# ICP_XMega.net
KiCad netlist of a schematic drawn in EAGLE
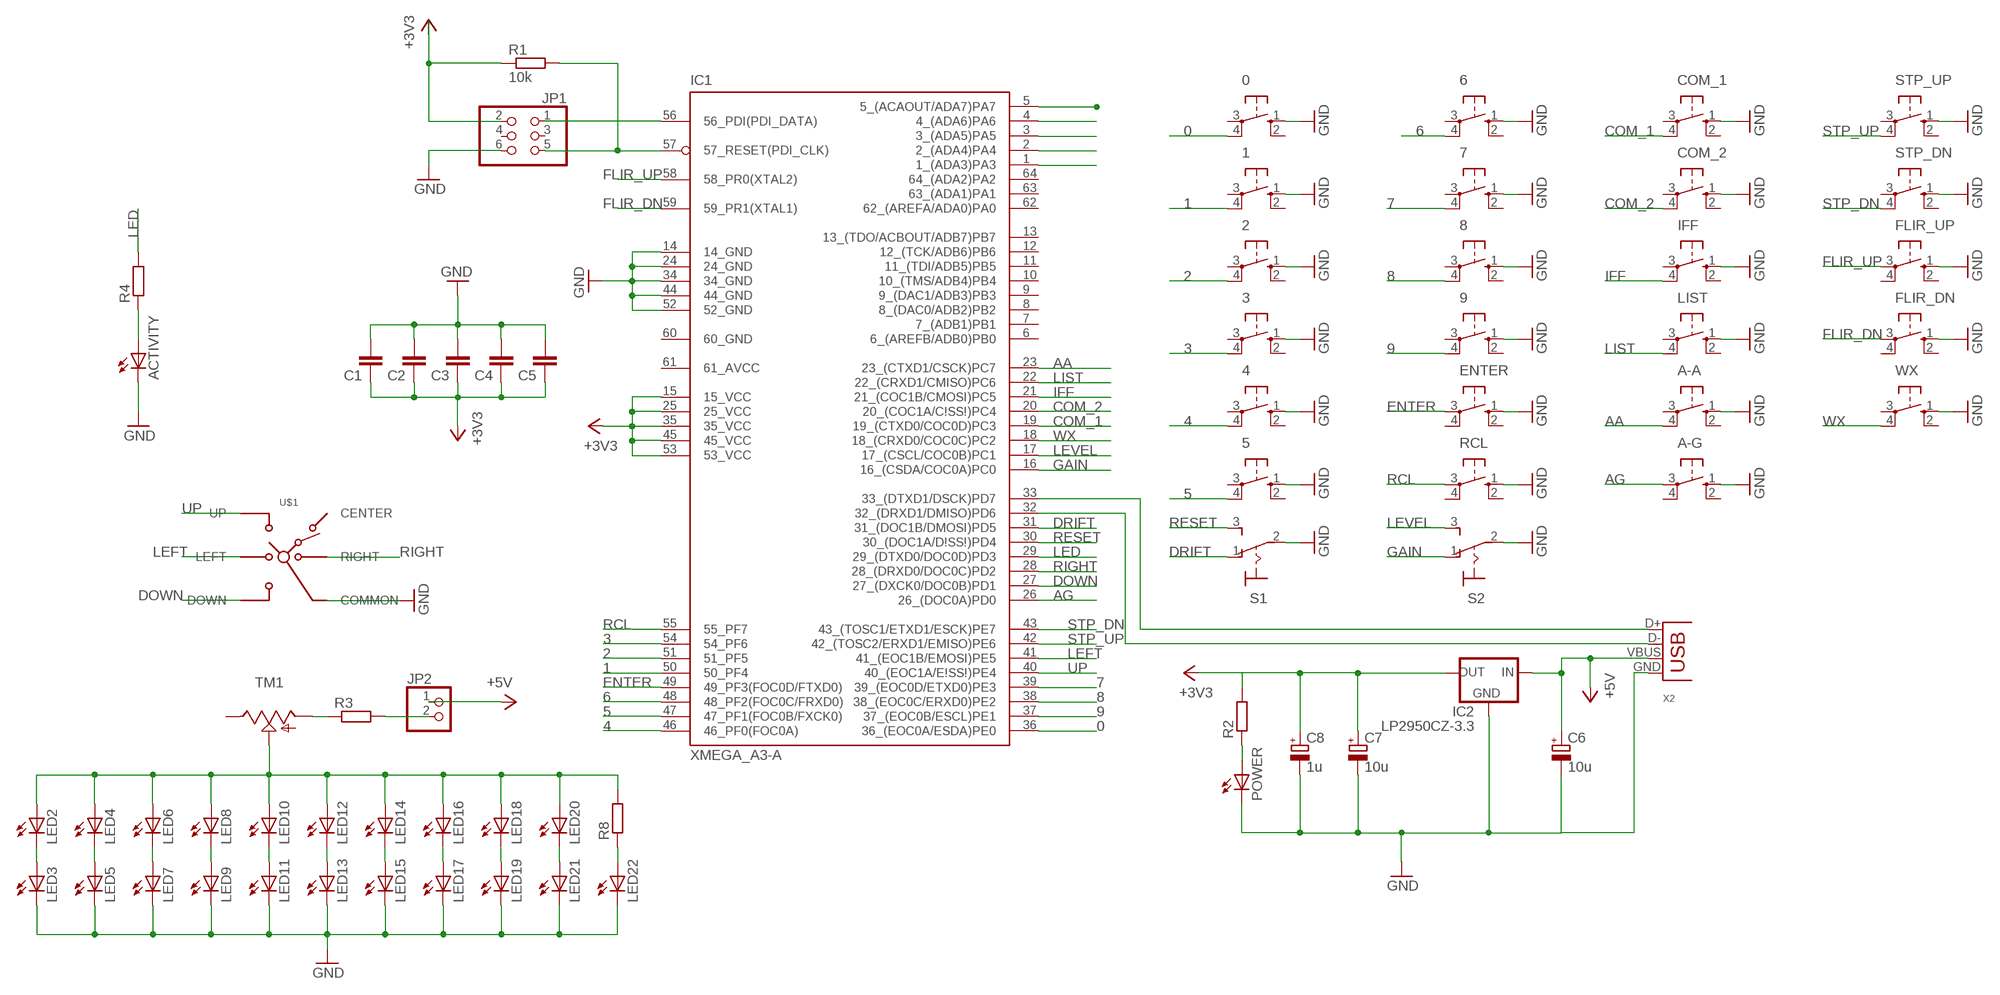
[diagram p0: schematic, sheet 1]

(export (version "E")
  (design (tool "Eeschema 10.0.6"))
  (components
    (comp (ref "0")
      (value "10-XX")
      (footprint "eagle-import:B3F-10XX")
      (fields (field (name "MPN") "B3F-1000"))
      (libsource (lib "eagle-import") (part "10-XX"))
    )
    (comp (ref "1")
      (value "10-XX")
      (footprint "eagle-import:B3F-10XX")
      (fields (field (name "MPN") "B3F-1000"))
      (libsource (lib "eagle-import") (part "10-XX"))
    )
    (comp (ref "2")
      (value "10-XX")
      (footprint "eagle-import:B3F-10XX")
      (fields (field (name "MPN") "B3F-1000"))
      (libsource (lib "eagle-import") (part "10-XX"))
    )
    (comp (ref "3")
      (value "10-XX")
      (footprint "eagle-import:B3F-10XX")
      (fields (field (name "MPN") "B3F-1000"))
      (libsource (lib "eagle-import") (part "10-XX"))
    )
    (comp (ref "4")
      (value "10-XX")
      (footprint "eagle-import:B3F-10XX")
      (fields (field (name "MPN") "B3F-1000"))
      (libsource (lib "eagle-import") (part "10-XX"))
    )
    (comp (ref "5")
      (value "10-XX")
      (footprint "eagle-import:B3F-10XX")
      (fields (field (name "MPN") "B3F-1000"))
      (libsource (lib "eagle-import") (part "10-XX"))
    )
    (comp (ref "6")
      (value "10-XX")
      (footprint "eagle-import:B3F-10XX")
      (fields (field (name "MPN") "B3F-1000"))
      (libsource (lib "eagle-import") (part "10-XX"))
    )
    (comp (ref "7")
      (value "10-XX")
      (footprint "eagle-import:B3F-10XX")
      (fields (field (name "MPN") "B3F-1000"))
      (libsource (lib "eagle-import") (part "10-XX"))
    )
    (comp (ref "8")
      (value "10-XX")
      (footprint "eagle-import:B3F-10XX")
      (fields (field (name "MPN") "B3F-1000"))
      (libsource (lib "eagle-import") (part "10-XX"))
    )
    (comp (ref "9")
      (value "10-XX")
      (footprint "eagle-import:B3F-10XX")
      (fields (field (name "MPN") "B3F-1000"))
      (libsource (lib "eagle-import") (part "10-XX"))
    )
    (comp (ref "A-A")
      (value "10-XX")
      (footprint "eagle-import:B3F-10XX")
      (fields (field (name "MPN") "B3F-1000"))
      (libsource (lib "eagle-import") (part "10-XX"))
    )
    (comp (ref "A-G")
      (value "10-XX")
      (footprint "eagle-import:B3F-10XX")
      (fields (field (name "MPN") "B3F-1000"))
      (libsource (lib "eagle-import") (part "10-XX"))
    )
    (comp (ref "ACTIVITY")
      (value "LEDSMT1206")
      (footprint "eagle-import:1206")
      (libsource (lib "eagle-import") (part "LEDSMT1206"))
    )
    (comp (ref "C1")
      (value "C-EUC1206")
      (footprint "eagle-import:C1206")
      (libsource (lib "eagle-import") (part "C-EUC1206"))
    )
    (comp (ref "C2")
      (value "C-EUC1206")
      (footprint "eagle-import:C1206")
      (libsource (lib "eagle-import") (part "C-EUC1206"))
    )
    (comp (ref "C3")
      (value "C-EUC1206")
      (footprint "eagle-import:C1206")
      (libsource (lib "eagle-import") (part "C-EUC1206"))
    )
    (comp (ref "C4")
      (value "C-EUC1206")
      (footprint "eagle-import:C1206")
      (libsource (lib "eagle-import") (part "C-EUC1206"))
    )
    (comp (ref "C5")
      (value "C-EUC1206")
      (footprint "eagle-import:C1206")
      (libsource (lib "eagle-import") (part "C-EUC1206"))
    )
    (comp (ref "C6")
      (value "10u")
      (footprint "eagle-import:E2,5-5")
      (libsource (lib "eagle-import") (part "CPOL-EUE2.5-5"))
    )
    (comp (ref "C7")
      (value "10u")
      (footprint "eagle-import:E2,5-5")
      (libsource (lib "eagle-import") (part "CPOL-EUE2.5-5"))
    )
    (comp (ref "C8")
      (value "1u")
      (footprint "eagle-import:C_6032-28R")
      (libsource (lib "eagle-import") (part "CPOL-EUC/6032-28R"))
    )
    (comp (ref "COM_1")
      (value "10-XX")
      (footprint "eagle-import:B3F-10XX")
      (fields (field (name "MPN") "B3F-1000"))
      (libsource (lib "eagle-import") (part "10-XX"))
    )
    (comp (ref "COM_2")
      (value "10-XX")
      (footprint "eagle-import:B3F-10XX")
      (fields (field (name "MPN") "B3F-1000"))
      (libsource (lib "eagle-import") (part "10-XX"))
    )
    (comp (ref "ENTER")
      (value "10-XX")
      (footprint "eagle-import:B3F-10XX")
      (fields (field (name "MPN") "B3F-1000"))
      (libsource (lib "eagle-import") (part "10-XX"))
    )
    (comp (ref "FLIR_DN")
      (value "10-XX")
      (footprint "eagle-import:B3F-10XX")
      (fields (field (name "MPN") "B3F-1000"))
      (libsource (lib "eagle-import") (part "10-XX"))
    )
    (comp (ref "FLIR_UP")
      (value "10-XX")
      (footprint "eagle-import:B3F-10XX")
      (fields (field (name "MPN") "B3F-1000"))
      (libsource (lib "eagle-import") (part "10-XX"))
    )
    (comp (ref "IC1")
      (value "XMEGA_A3-A")
      (footprint "eagle-import:TQFP64")
      (libsource (lib "eagle-import") (part "XMEGA_A3-A"))
    )
    (comp (ref "IC2")
      (value "LP2950CZ-3.3")
      (footprint "eagle-import:TO92")
      (libsource (lib "eagle-import") (part "LP2950?CZ-3.3"))
    )
    (comp (ref "IFF")
      (value "10-XX")
      (footprint "eagle-import:B3F-10XX")
      (fields (field (name "MPN") "B3F-1000"))
      (libsource (lib "eagle-import") (part "10-XX"))
    )
    (comp (ref "JP1")
      (value "PINHD-2X3")
      (footprint "eagle-import:2X03")
      (libsource (lib "eagle-import") (part "PINHD-2X3"))
    )
    (comp (ref "JP2")
      (value "PINHD-1X2")
      (footprint "eagle-import:1X02")
      (libsource (lib "eagle-import") (part "PINHD-1X2"))
    )
    (comp (ref "LED2")
      (value "LEDSMT1206")
      (footprint "eagle-import:1206")
      (libsource (lib "eagle-import") (part "LEDSMT1206"))
    )
    (comp (ref "LED3")
      (value "LEDSMT1206")
      (footprint "eagle-import:1206")
      (libsource (lib "eagle-import") (part "LEDSMT1206"))
    )
    (comp (ref "LED4")
      (value "LEDSMT1206")
      (footprint "eagle-import:1206")
      (libsource (lib "eagle-import") (part "LEDSMT1206"))
    )
    (comp (ref "LED5")
      (value "LEDSMT1206")
      (footprint "eagle-import:1206")
      (libsource (lib "eagle-import") (part "LEDSMT1206"))
    )
    (comp (ref "LED6")
      (value "LEDSMT1206")
      (footprint "eagle-import:1206")
      (libsource (lib "eagle-import") (part "LEDSMT1206"))
    )
    (comp (ref "LED7")
      (value "LEDSMT1206")
      (footprint "eagle-import:1206")
      (libsource (lib "eagle-import") (part "LEDSMT1206"))
    )
    (comp (ref "LED8")
      (value "LEDSMT1206")
      (footprint "eagle-import:1206")
      (libsource (lib "eagle-import") (part "LEDSMT1206"))
    )
    (comp (ref "LED9")
      (value "LEDSMT1206")
      (footprint "eagle-import:1206")
      (libsource (lib "eagle-import") (part "LEDSMT1206"))
    )
    (comp (ref "LED10")
      (value "LEDSMT1206")
      (footprint "eagle-import:1206")
      (libsource (lib "eagle-import") (part "LEDSMT1206"))
    )
    (comp (ref "LED11")
      (value "LEDSMT1206")
      (footprint "eagle-import:1206")
      (libsource (lib "eagle-import") (part "LEDSMT1206"))
    )
    (comp (ref "LED12")
      (value "LEDSMT1206")
      (footprint "eagle-import:1206")
      (libsource (lib "eagle-import") (part "LEDSMT1206"))
    )
    (comp (ref "LED13")
      (value "LEDSMT1206")
      (footprint "eagle-import:1206")
      (libsource (lib "eagle-import") (part "LEDSMT1206"))
    )
    (comp (ref "LED14")
      (value "LEDSMT1206")
      (footprint "eagle-import:1206")
      (libsource (lib "eagle-import") (part "LEDSMT1206"))
    )
    (comp (ref "LED15")
      (value "LEDSMT1206")
      (footprint "eagle-import:1206")
      (libsource (lib "eagle-import") (part "LEDSMT1206"))
    )
    (comp (ref "LED16")
      (value "LEDSMT1206")
      (footprint "eagle-import:1206")
      (libsource (lib "eagle-import") (part "LEDSMT1206"))
    )
    (comp (ref "LED17")
      (value "LEDSMT1206")
      (footprint "eagle-import:1206")
      (libsource (lib "eagle-import") (part "LEDSMT1206"))
    )
    (comp (ref "LED18")
      (value "LEDSMT1206")
      (footprint "eagle-import:1206")
      (libsource (lib "eagle-import") (part "LEDSMT1206"))
    )
    (comp (ref "LED19")
      (value "LEDSMT1206")
      (footprint "eagle-import:1206")
      (libsource (lib "eagle-import") (part "LEDSMT1206"))
    )
    (comp (ref "LED20")
      (value "LEDSMT1206")
      (footprint "eagle-import:1206")
      (libsource (lib "eagle-import") (part "LEDSMT1206"))
    )
    (comp (ref "LED21")
      (value "LEDSMT1206")
      (footprint "eagle-import:1206")
      (libsource (lib "eagle-import") (part "LEDSMT1206"))
    )
    (comp (ref "LED22")
      (value "LEDSMT1206")
      (footprint "eagle-import:1206")
      (libsource (lib "eagle-import") (part "LEDSMT1206"))
    )
    (comp (ref "LIST")
      (value "10-XX")
      (footprint "eagle-import:B3F-10XX")
      (fields (field (name "MPN") "B3F-1000"))
      (libsource (lib "eagle-import") (part "10-XX"))
    )
    (comp (ref "POWER")
      (value "LEDSMT1206")
      (footprint "eagle-import:1206")
      (libsource (lib "eagle-import") (part "LEDSMT1206"))
    )
    (comp (ref "R1")
      (value "10k")
      (footprint "eagle-import:R1206")
      (libsource (lib "eagle-import") (part "R-EU_R1206"))
    )
    (comp (ref "R2")
      (value "R-EU_M1206")
      (footprint "eagle-import:M1206")
      (libsource (lib "eagle-import") (part "R-EU_M1206"))
    )
    (comp (ref "R3")
      (value "R-EU_0204/7")
      (footprint "eagle-import:0204_7")
      (libsource (lib "eagle-import") (part "R-EU_0204/7"))
    )
    (comp (ref "R4")
      (value "R-EU_M1206")
      (footprint "eagle-import:M1206")
      (libsource (lib "eagle-import") (part "R-EU_M1206"))
    )
    (comp (ref "R8")
      (value "R-EU_M1206")
      (footprint "eagle-import:M1206")
      (libsource (lib "eagle-import") (part "R-EU_M1206"))
    )
    (comp (ref "RCL")
      (value "10-XX")
      (footprint "eagle-import:B3F-10XX")
      (fields (field (name "MPN") "B3F-1000"))
      (libsource (lib "eagle-import") (part "10-XX"))
    )
    (comp (ref "S1")
      (value "320-916")
      (footprint "eagle-import:320-916")
      (libsource (lib "eagle-import") (part "320-916"))
    )
    (comp (ref "S2")
      (value "320-916")
      (footprint "eagle-import:320-916")
      (libsource (lib "eagle-import") (part "320-916"))
    )
    (comp (ref "STP_DN")
      (value "10-XX")
      (footprint "eagle-import:B3F-10XX")
      (fields (field (name "MPN") "B3F-1000"))
      (libsource (lib "eagle-import") (part "10-XX"))
    )
    (comp (ref "STP_UP")
      (value "10-XX")
      (footprint "eagle-import:B3F-10XX")
      (fields (field (name "MPN") "B3F-1000"))
      (libsource (lib "eagle-import") (part "10-XX"))
    )
    (comp (ref "TM1")
      (value "TRIM")
      (footprint "eagle-import:6MM")
      (libsource (lib "eagle-import") (part "TRIM"))
    )
    (comp (ref "U$1")
      (value "SKQUCAA010")
      (footprint "eagle-import:SKQU")
      (fields (field (name "MF") "ALPS"))
      (libsource (lib "eagle-import") (part "SKQUCAA010"))
    )
    (comp (ref "WX")
      (value "10-XX")
      (footprint "eagle-import:B3F-10XX")
      (fields (field (name "MPN") "B3F-1000"))
      (libsource (lib "eagle-import") (part "10-XX"))
    )
    (comp (ref "X2")
      (value "USB-B-H")
      (footprint "eagle-import:USB-B-H")
      (libsource (lib "eagle-import") (part "USB-B-H"))
    )
  )
  (nets
    (net (code "1") (name "+3V3") (class "Default")
      (node (ref "C1") (pin "1") (pinfunction "1_1") (pintype "passive"))
      (node (ref "C2") (pin "1") (pinfunction "1_1") (pintype "passive"))
      (node (ref "C3") (pin "1") (pinfunction "1_1") (pintype "passive"))
      (node (ref "C4") (pin "1") (pinfunction "1_1") (pintype "passive"))
      (node (ref "C5") (pin "1") (pinfunction "1_1") (pintype "passive"))
      (node (ref "C7") (pin "+") (pinfunction "+_+") (pintype "passive"))
      (node (ref "C8") (pin "+") (pinfunction "+_+") (pintype "passive"))
      (node (ref "IC1") (pin "15") (pinfunction "15_VCC_15") (pintype "bidirectional"))
      (node (ref "IC1") (pin "25") (pinfunction "25_VCC_25") (pintype "bidirectional"))
      (node (ref "IC1") (pin "35") (pinfunction "35_VCC_35") (pintype "bidirectional"))
      (node (ref "IC1") (pin "45") (pinfunction "45_VCC_45") (pintype "bidirectional"))
      (node (ref "IC1") (pin "53") (pinfunction "53_VCC_53") (pintype "bidirectional"))
      (node (ref "IC2") (pin "1") (pinfunction "OUT_1") (pintype "passive"))
      (node (ref "JP1") (pin "2") (pinfunction "2_2") (pintype "passive"))
      (node (ref "R1") (pin "1") (pinfunction "1_1") (pintype "passive"))
      (node (ref "R2") (pin "2") (pinfunction "2_2") (pintype "passive"))
    )
    (net (code "2") (name "+5V") (class "Default")
      (node (ref "C6") (pin "+") (pinfunction "+_+") (pintype "passive"))
      (node (ref "IC2") (pin "3") (pinfunction "IN_3") (pintype "input"))
      (node (ref "JP2") (pin "1") (pinfunction "1_1") (pintype "passive"))
      (node (ref "X2") (pin "VBUS") (pinfunction "VBUS_VBUS") (pintype "bidirectional"))
    )
    (net (code "3") (name "/0") (class "Default")
      (node (ref "0") (pin "4") (pinfunction "P1_4") (pintype "passive"))
      (node (ref "IC1") (pin "36") (pinfunction "36_(EOC0A/ESDA)PE0_36") (pintype "bidirectional"))
    )
    (net (code "4") (name "/1") (class "Default")
      (node (ref "1") (pin "4") (pinfunction "P1_4") (pintype "passive"))
      (node (ref "IC1") (pin "50") (pinfunction "50_PF4_50") (pintype "bidirectional"))
    )
    (net (code "5") (name "/2") (class "Default")
      (node (ref "2") (pin "4") (pinfunction "P1_4") (pintype "passive"))
      (node (ref "IC1") (pin "51") (pinfunction "51_PF5_51") (pintype "bidirectional"))
    )
    (net (code "6") (name "/3") (class "Default")
      (node (ref "3") (pin "4") (pinfunction "P1_4") (pintype "passive"))
      (node (ref "IC1") (pin "54") (pinfunction "54_PF6_54") (pintype "bidirectional"))
    )
    (net (code "7") (name "/4") (class "Default")
      (node (ref "4") (pin "4") (pinfunction "P1_4") (pintype "passive"))
      (node (ref "IC1") (pin "46") (pinfunction "46_PF0(FOC0A)_46") (pintype "bidirectional"))
    )
    (net (code "8") (name "/5") (class "Default")
      (node (ref "5") (pin "4") (pinfunction "P1_4") (pintype "passive"))
      (node (ref "IC1") (pin "47") (pinfunction "47_PF1(FOC0B/FXCK0)_47") (pintype "bidirectional"))
    )
    (net (code "9") (name "/6") (class "Default")
      (node (ref "6") (pin "4") (pinfunction "P1_4") (pintype "passive"))
      (node (ref "IC1") (pin "48") (pinfunction "48_PF2(FOC0C/FRXD0)_48") (pintype "bidirectional"))
    )
    (net (code "10") (name "/7") (class "Default")
      (node (ref "7") (pin "4") (pinfunction "P1_4") (pintype "passive"))
      (node (ref "IC1") (pin "39") (pinfunction "39_(EOC0D/ETXD0)PE3_39") (pintype "bidirectional"))
    )
    (net (code "11") (name "/8") (class "Default")
      (node (ref "8") (pin "4") (pinfunction "P1_4") (pintype "passive"))
      (node (ref "IC1") (pin "38") (pinfunction "38_(EOC0C/ERXD0)PE2_38") (pintype "bidirectional"))
    )
    (net (code "12") (name "/9") (class "Default")
      (node (ref "9") (pin "4") (pinfunction "P1_4") (pintype "passive"))
      (node (ref "IC1") (pin "37") (pinfunction "37_(EOC0B/ESCL)PE1_37") (pintype "bidirectional"))
    )
    (net (code "13") (name "/AA") (class "Default")
      (node (ref "A-A") (pin "4") (pinfunction "P1_4") (pintype "passive"))
      (node (ref "IC1") (pin "23") (pinfunction "23_(CTXD1/CSCK)PC7_23") (pintype "bidirectional"))
    )
    (net (code "14") (name "/AG") (class "Default")
      (node (ref "A-G") (pin "3") (pinfunction "P_3") (pintype "passive"))
      (node (ref "IC1") (pin "26") (pinfunction "26_(DOC0A)PD0_26") (pintype "bidirectional"))
    )
    (net (code "15") (name "/COM_1") (class "Default")
      (node (ref "COM_1") (pin "4") (pinfunction "P1_4") (pintype "passive"))
      (node (ref "IC1") (pin "19") (pinfunction "19_(CTXD0/COC0D)PC3_19") (pintype "bidirectional"))
    )
    (net (code "16") (name "/COM_2") (class "Default")
      (node (ref "COM_2") (pin "4") (pinfunction "P1_4") (pintype "passive"))
      (node (ref "IC1") (pin "20") (pinfunction "20_(COC1A/C\\~{SS\\})PC4_20") (pintype "bidirectional"))
    )
    (net (code "17") (name "/DOWN") (class "Default")
      (node (ref "IC1") (pin "27") (pinfunction "27_(DXCK0/DOC0B)PD1_27") (pintype "bidirectional"))
      (node (ref "U$1") (pin "DOWN") (pinfunction "DOWN_DOWN") (pintype "passive"))
    )
    (net (code "18") (name "/DRIFT") (class "Default")
      (node (ref "IC1") (pin "31") (pinfunction "31_(DOC1B/DMOSI)PD5_31") (pintype "bidirectional"))
      (node (ref "S1") (pin "1") (pinfunction "O_1") (pintype "passive"))
    )
    (net (code "19") (name "/ENTER") (class "Default")
      (node (ref "ENTER") (pin "3") (pinfunction "P_3") (pintype "passive"))
      (node (ref "IC1") (pin "49") (pinfunction "49_PF3(FOC0D/FTXD0)_49") (pintype "bidirectional"))
    )
    (net (code "20") (name "/FLIR_DN") (class "Default")
      (node (ref "FLIR_DN") (pin "3") (pinfunction "P_3") (pintype "passive"))
      (node (ref "IC1") (pin "59") (pinfunction "59_PR1(XTAL1)_59") (pintype "bidirectional"))
    )
    (net (code "21") (name "/FLIR_UP") (class "Default")
      (node (ref "FLIR_UP") (pin "3") (pinfunction "P_3") (pintype "passive"))
      (node (ref "IC1") (pin "58") (pinfunction "58_PR0(XTAL2)_58") (pintype "bidirectional"))
    )
    (net (code "22") (name "/GAIN") (class "Default")
      (node (ref "IC1") (pin "16") (pinfunction "16_(CSDA/COC0A)PC0_16") (pintype "bidirectional"))
      (node (ref "S2") (pin "1") (pinfunction "O_1") (pintype "passive"))
    )
    (net (code "23") (name "/IFF") (class "Default")
      (node (ref "IC1") (pin "21") (pinfunction "21_(COC1B/CMOSI)PC5_21") (pintype "bidirectional"))
      (node (ref "IFF") (pin "4") (pinfunction "P1_4") (pintype "passive"))
    )
    (net (code "24") (name "/LED") (class "Default")
      (node (ref "IC1") (pin "29") (pinfunction "29_(DTXD0/DOC0D)PD3_29") (pintype "bidirectional"))
      (node (ref "R4") (pin "2") (pinfunction "2_2") (pintype "passive"))
    )
    (net (code "25") (name "/LEFT") (class "Default")
      (node (ref "IC1") (pin "41") (pinfunction "41_(EOC1B/EMOSI)PE5_41") (pintype "bidirectional"))
      (node (ref "U$1") (pin "LEFT") (pinfunction "LEFT_LEFT") (pintype "passive"))
    )
    (net (code "26") (name "/LEVEL") (class "Default")
      (node (ref "IC1") (pin "17") (pinfunction "17_(CSCL/COC0B)PC1_17") (pintype "bidirectional"))
      (node (ref "S2") (pin "3") (pinfunction "S_3") (pintype "passive"))
    )
    (net (code "27") (name "/LIST") (class "Default")
      (node (ref "IC1") (pin "22") (pinfunction "22_(CRXD1/CMISO)PC6_22") (pintype "bidirectional"))
      (node (ref "LIST") (pin "4") (pinfunction "P1_4") (pintype "passive"))
    )
    (net (code "28") (name "/RCL") (class "Default")
      (node (ref "IC1") (pin "55") (pinfunction "55_PF7_55") (pintype "bidirectional"))
      (node (ref "RCL") (pin "3") (pinfunction "P_3") (pintype "passive"))
    )
    (net (code "29") (name "/RESET") (class "Default")
      (node (ref "IC1") (pin "30") (pinfunction "30_(DOC1A/D\\~{SS\\})PD4_30") (pintype "bidirectional"))
      (node (ref "S1") (pin "3") (pinfunction "S_3") (pintype "passive"))
    )
    (net (code "30") (name "/RIGHT") (class "Default")
      (node (ref "IC1") (pin "28") (pinfunction "28_(DRXD0/DOC0C)PD2_28") (pintype "bidirectional"))
      (node (ref "U$1") (pin "RIGHT") (pinfunction "RIGHT_RIGHT") (pintype "passive"))
    )
    (net (code "31") (name "/STP_DN") (class "Default")
      (node (ref "IC1") (pin "43") (pinfunction "43_(TOSC1/ETXD1/ESCK)PE7_43") (pintype "bidirectional"))
      (node (ref "STP_DN") (pin "4") (pinfunction "P1_4") (pintype "passive"))
    )
    (net (code "32") (name "/STP_UP") (class "Default")
      (node (ref "IC1") (pin "42") (pinfunction "42_(TOSC2/ERXD1/EMISO)PE6_42") (pintype "bidirectional"))
      (node (ref "STP_UP") (pin "4") (pinfunction "P1_4") (pintype "passive"))
    )
    (net (code "33") (name "/UP") (class "Default")
      (node (ref "IC1") (pin "40") (pinfunction "40_(EOC1A/E\\~{SS\\})PE4_40") (pintype "bidirectional"))
      (node (ref "U$1") (pin "UP") (pinfunction "UP_UP") (pintype "passive"))
    )
    (net (code "34") (name "/WX") (class "Default")
      (node (ref "IC1") (pin "18") (pinfunction "18_(CRXD0/COC0C)PC2_18") (pintype "bidirectional"))
      (node (ref "WX") (pin "4") (pinfunction "P1_4") (pintype "passive"))
    )
    (net (code "35") (name "GND") (class "Default")
      (node (ref "0") (pin "1") (pinfunction "S_1") (pintype "passive"))
      (node (ref "1") (pin "1") (pinfunction "S_1") (pintype "passive"))
      (node (ref "2") (pin "1") (pinfunction "S_1") (pintype "passive"))
      (node (ref "3") (pin "1") (pinfunction "S_1") (pintype "passive"))
      (node (ref "4") (pin "1") (pinfunction "S_1") (pintype "passive"))
      (node (ref "5") (pin "1") (pinfunction "S_1") (pintype "passive"))
      (node (ref "6") (pin "1") (pinfunction "S_1") (pintype "passive"))
      (node (ref "7") (pin "1") (pinfunction "S_1") (pintype "passive"))
      (node (ref "8") (pin "1") (pinfunction "S_1") (pintype "passive"))
      (node (ref "9") (pin "1") (pinfunction "S_1") (pintype "passive"))
      (node (ref "A-A") (pin "1") (pinfunction "S_1") (pintype "passive"))
      (node (ref "A-G") (pin "1") (pinfunction "S_1") (pintype "passive"))
      (node (ref "ACTIVITY") (pin "C") (pinfunction "C_C") (pintype "passive"))
      (node (ref "C1") (pin "2") (pinfunction "2_2") (pintype "passive"))
      (node (ref "C2") (pin "2") (pinfunction "2_2") (pintype "passive"))
      (node (ref "C3") (pin "2") (pinfunction "2_2") (pintype "passive"))
      (node (ref "C4") (pin "2") (pinfunction "2_2") (pintype "passive"))
      (node (ref "C5") (pin "2") (pinfunction "2_2") (pintype "passive"))
      (node (ref "C6") (pin "-") (pinfunction "-_-") (pintype "passive"))
      (node (ref "C7") (pin "-") (pinfunction "-_-") (pintype "passive"))
      (node (ref "C8") (pin "-") (pinfunction "-_-") (pintype "passive"))
      (node (ref "COM_1") (pin "1") (pinfunction "S_1") (pintype "passive"))
      (node (ref "COM_2") (pin "1") (pinfunction "S_1") (pintype "passive"))
      (node (ref "ENTER") (pin "1") (pinfunction "S_1") (pintype "passive"))
      (node (ref "FLIR_DN") (pin "1") (pinfunction "S_1") (pintype "passive"))
      (node (ref "FLIR_UP") (pin "1") (pinfunction "S_1") (pintype "passive"))
      (node (ref "IC1") (pin "14") (pinfunction "14_GND_14") (pintype "bidirectional"))
      (node (ref "IC1") (pin "24") (pinfunction "24_GND_24") (pintype "bidirectional"))
      (node (ref "IC1") (pin "34") (pinfunction "34_GND_34") (pintype "bidirectional"))
      (node (ref "IC1") (pin "44") (pinfunction "44_GND_44") (pintype "bidirectional"))
      (node (ref "IC1") (pin "52") (pinfunction "52_GND_52") (pintype "bidirectional"))
      (node (ref "IC2") (pin "2") (pinfunction "GND_2") (pintype "input"))
      (node (ref "IFF") (pin "1") (pinfunction "S_1") (pintype "passive"))
      (node (ref "JP1") (pin "6") (pinfunction "6_6") (pintype "passive"))
      (node (ref "LED11") (pin "C") (pinfunction "C_C") (pintype "passive"))
      (node (ref "LED13") (pin "C") (pinfunction "C_C") (pintype "passive"))
      (node (ref "LED15") (pin "C") (pinfunction "C_C") (pintype "passive"))
      (node (ref "LED17") (pin "C") (pinfunction "C_C") (pintype "passive"))
      (node (ref "LED19") (pin "C") (pinfunction "C_C") (pintype "passive"))
      (node (ref "LED21") (pin "C") (pinfunction "C_C") (pintype "passive"))
      (node (ref "LED22") (pin "C") (pinfunction "C_C") (pintype "passive"))
      (node (ref "LED3") (pin "C") (pinfunction "C_C") (pintype "passive"))
      (node (ref "LED5") (pin "C") (pinfunction "C_C") (pintype "passive"))
      (node (ref "LED7") (pin "C") (pinfunction "C_C") (pintype "passive"))
      (node (ref "LED9") (pin "C") (pinfunction "C_C") (pintype "passive"))
      (node (ref "LIST") (pin "1") (pinfunction "S_1") (pintype "passive"))
      (node (ref "POWER") (pin "C") (pinfunction "C_C") (pintype "passive"))
      (node (ref "RCL") (pin "1") (pinfunction "S_1") (pintype "passive"))
      (node (ref "S1") (pin "2") (pinfunction "P_2") (pintype "passive"))
      (node (ref "S2") (pin "2") (pinfunction "P_2") (pintype "passive"))
      (node (ref "STP_DN") (pin "1") (pinfunction "S_1") (pintype "passive"))
      (node (ref "STP_UP") (pin "1") (pinfunction "S_1") (pintype "passive"))
      (node (ref "U$1") (pin "COMMON") (pinfunction "COMMON_COMMON") (pintype "power_in"))
      (node (ref "WX") (pin "1") (pinfunction "S_1") (pintype "passive"))
      (node (ref "X2") (pin "GND") (pinfunction "GND_GND") (pintype "bidirectional"))
    )
    (net (code "36") (name "Net-(ACTIVITY-PadA)") (class "Default")
      (node (ref "ACTIVITY") (pin "A") (pinfunction "A_A") (pintype "passive"))
      (node (ref "R4") (pin "1") (pinfunction "1_1") (pintype "passive"))
    )
    (net (code "37") (name "Net-(IC1-32_(DRXD1{slash}DMISO)PD6)") (class "Default")
      (node (ref "IC1") (pin "32") (pinfunction "32_(DRXD1/DMISO)PD6_32") (pintype "bidirectional"))
      (node (ref "X2") (pin "D-") (pinfunction "D-_D-") (pintype "bidirectional"))
    )
    (net (code "38") (name "Net-(IC1-33_(DTXD1{slash}DSCK)PD7)") (class "Default")
      (node (ref "IC1") (pin "33") (pinfunction "33_(DTXD1/DSCK)PD7_33") (pintype "bidirectional"))
      (node (ref "X2") (pin "D+") (pinfunction "D+_D+") (pintype "bidirectional"))
    )
    (net (code "39") (name "Net-(IC1-56_PDI(PDI_DATA))") (class "Default")
      (node (ref "IC1") (pin "56") (pinfunction "56_PDI(PDI_DATA)_56") (pintype "bidirectional"))
      (node (ref "JP1") (pin "1") (pinfunction "1_1") (pintype "passive"))
    )
    (net (code "40") (name "Net-(IC1-57_RESET(PDI_CLK))") (class "Default")
      (node (ref "IC1") (pin "57") (pinfunction "57_RESET(PDI_CLK)_57") (pintype "bidirectional"))
      (node (ref "JP1") (pin "5") (pinfunction "5_5") (pintype "passive"))
      (node (ref "R1") (pin "2") (pinfunction "2_2") (pintype "passive"))
    )
    (net (code "41") (name "Net-(JP2-Pad2)") (class "Default")
      (node (ref "JP2") (pin "2") (pinfunction "2_2") (pintype "passive"))
      (node (ref "R3") (pin "2") (pinfunction "2_2") (pintype "passive"))
    )
    (net (code "42") (name "Net-(LED2-PadC)") (class "Default")
      (node (ref "LED2") (pin "C") (pinfunction "C_C") (pintype "passive"))
      (node (ref "LED3") (pin "A") (pinfunction "A_A") (pintype "passive"))
    )
    (net (code "43") (name "Net-(LED4-PadC)") (class "Default")
      (node (ref "LED4") (pin "C") (pinfunction "C_C") (pintype "passive"))
      (node (ref "LED5") (pin "A") (pinfunction "A_A") (pintype "passive"))
    )
    (net (code "44") (name "Net-(LED6-PadC)") (class "Default")
      (node (ref "LED6") (pin "C") (pinfunction "C_C") (pintype "passive"))
      (node (ref "LED7") (pin "A") (pinfunction "A_A") (pintype "passive"))
    )
    (net (code "45") (name "Net-(LED8-PadC)") (class "Default")
      (node (ref "LED8") (pin "C") (pinfunction "C_C") (pintype "passive"))
      (node (ref "LED9") (pin "A") (pinfunction "A_A") (pintype "passive"))
    )
    (net (code "46") (name "Net-(LED10-PadA)") (class "Default")
      (node (ref "LED10") (pin "A") (pinfunction "A_A") (pintype "passive"))
      (node (ref "LED12") (pin "A") (pinfunction "A_A") (pintype "passive"))
      (node (ref "LED14") (pin "A") (pinfunction "A_A") (pintype "passive"))
      (node (ref "LED16") (pin "A") (pinfunction "A_A") (pintype "passive"))
      (node (ref "LED18") (pin "A") (pinfunction "A_A") (pintype "passive"))
      (node (ref "LED2") (pin "A") (pinfunction "A_A") (pintype "passive"))
      (node (ref "LED20") (pin "A") (pinfunction "A_A") (pintype "passive"))
      (node (ref "LED4") (pin "A") (pinfunction "A_A") (pintype "passive"))
      (node (ref "LED6") (pin "A") (pinfunction "A_A") (pintype "passive"))
      (node (ref "LED8") (pin "A") (pinfunction "A_A") (pintype "passive"))
      (node (ref "R8") (pin "2") (pinfunction "2_2") (pintype "passive"))
      (node (ref "TM1") (pin "S") (pinfunction "S_S") (pintype "passive"))
    )
    (net (code "47") (name "Net-(LED10-PadC)") (class "Default")
      (node (ref "LED10") (pin "C") (pinfunction "C_C") (pintype "passive"))
      (node (ref "LED11") (pin "A") (pinfunction "A_A") (pintype "passive"))
    )
    (net (code "48") (name "Net-(LED12-PadC)") (class "Default")
      (node (ref "LED12") (pin "C") (pinfunction "C_C") (pintype "passive"))
      (node (ref "LED13") (pin "A") (pinfunction "A_A") (pintype "passive"))
    )
    (net (code "49") (name "Net-(LED14-PadC)") (class "Default")
      (node (ref "LED14") (pin "C") (pinfunction "C_C") (pintype "passive"))
      (node (ref "LED15") (pin "A") (pinfunction "A_A") (pintype "passive"))
    )
    (net (code "50") (name "Net-(LED16-PadC)") (class "Default")
      (node (ref "LED16") (pin "C") (pinfunction "C_C") (pintype "passive"))
      (node (ref "LED17") (pin "A") (pinfunction "A_A") (pintype "passive"))
    )
    (net (code "51") (name "Net-(LED18-PadC)") (class "Default")
      (node (ref "LED18") (pin "C") (pinfunction "C_C") (pintype "passive"))
      (node (ref "LED19") (pin "A") (pinfunction "A_A") (pintype "passive"))
    )
    (net (code "52") (name "Net-(LED20-PadC)") (class "Default")
      (node (ref "LED20") (pin "C") (pinfunction "C_C") (pintype "passive"))
      (node (ref "LED21") (pin "A") (pinfunction "A_A") (pintype "passive"))
    )
    (net (code "53") (name "Net-(LED22-PadA)") (class "Default")
      (node (ref "LED22") (pin "A") (pinfunction "A_A") (pintype "passive"))
      (node (ref "R8") (pin "1") (pinfunction "1_1") (pintype "passive"))
    )
    (net (code "54") (name "Net-(POWER-PadA)") (class "Default")
      (node (ref "POWER") (pin "A") (pinfunction "A_A") (pintype "passive"))
      (node (ref "R2") (pin "1") (pinfunction "1_1") (pintype "passive"))
    )
    (net (code "55") (name "Net-(R3-Pad1)") (class "Default")
      (node (ref "R3") (pin "1") (pinfunction "1_1") (pintype "passive"))
      (node (ref "TM1") (pin "A") (pinfunction "A_A") (pintype "passive"))
    )
    (net (code "56") (name "unconnected-(0-P-Pad3)") (class "Default")
      (node (ref "0") (pin "3") (pinfunction "P_3") (pintype "passive"))
    )
    (net (code "57") (name "unconnected-(0-S1-Pad2)") (class "Default")
      (node (ref "0") (pin "2") (pinfunction "S1_2") (pintype "passive"))
    )
    (net (code "58") (name "unconnected-(1-P-Pad3)") (class "Default")
      (node (ref "1") (pin "3") (pinfunction "P_3") (pintype "passive"))
    )
    (net (code "59") (name "unconnected-(1-S1-Pad2)") (class "Default")
      (node (ref "1") (pin "2") (pinfunction "S1_2") (pintype "passive"))
    )
    (net (code "60") (name "unconnected-(2-P-Pad3)") (class "Default")
      (node (ref "2") (pin "3") (pinfunction "P_3") (pintype "passive"))
    )
    (net (code "61") (name "unconnected-(2-S1-Pad2)") (class "Default")
      (node (ref "2") (pin "2") (pinfunction "S1_2") (pintype "passive"))
    )
    (net (code "62") (name "unconnected-(3-P-Pad3)") (class "Default")
      (node (ref "3") (pin "3") (pinfunction "P_3") (pintype "passive"))
    )
    (net (code "63") (name "unconnected-(3-S1-Pad2)") (class "Default")
      (node (ref "3") (pin "2") (pinfunction "S1_2") (pintype "passive"))
    )
    (net (code "64") (name "unconnected-(4-P-Pad3)") (class "Default")
      (node (ref "4") (pin "3") (pinfunction "P_3") (pintype "passive"))
    )
    (net (code "65") (name "unconnected-(4-S1-Pad2)") (class "Default")
      (node (ref "4") (pin "2") (pinfunction "S1_2") (pintype "passive"))
    )
    (net (code "66") (name "unconnected-(5-P-Pad3)") (class "Default")
      (node (ref "5") (pin "3") (pinfunction "P_3") (pintype "passive"))
    )
    (net (code "67") (name "unconnected-(5-S1-Pad2)") (class "Default")
      (node (ref "5") (pin "2") (pinfunction "S1_2") (pintype "passive"))
    )
    (net (code "68") (name "unconnected-(6-P-Pad3)") (class "Default")
      (node (ref "6") (pin "3") (pinfunction "P_3") (pintype "passive"))
    )
    (net (code "69") (name "unconnected-(6-S1-Pad2)") (class "Default")
      (node (ref "6") (pin "2") (pinfunction "S1_2") (pintype "passive"))
    )
    (net (code "70") (name "unconnected-(7-P-Pad3)") (class "Default")
      (node (ref "7") (pin "3") (pinfunction "P_3") (pintype "passive"))
    )
    (net (code "71") (name "unconnected-(7-S1-Pad2)") (class "Default")
      (node (ref "7") (pin "2") (pinfunction "S1_2") (pintype "passive"))
    )
    (net (code "72") (name "unconnected-(8-P-Pad3)") (class "Default")
      (node (ref "8") (pin "3") (pinfunction "P_3") (pintype "passive"))
    )
    (net (code "73") (name "unconnected-(8-S1-Pad2)") (class "Default")
      (node (ref "8") (pin "2") (pinfunction "S1_2") (pintype "passive"))
    )
    (net (code "74") (name "unconnected-(9-P-Pad3)") (class "Default")
      (node (ref "9") (pin "3") (pinfunction "P_3") (pintype "passive"))
    )
    (net (code "75") (name "unconnected-(9-S1-Pad2)") (class "Default")
      (node (ref "9") (pin "2") (pinfunction "S1_2") (pintype "passive"))
    )
    (net (code "76") (name "unconnected-(A-A-P-Pad3)") (class "Default")
      (node (ref "A-A") (pin "3") (pinfunction "P_3") (pintype "passive"))
    )
    (net (code "77") (name "unconnected-(A-A-S1-Pad2)") (class "Default")
      (node (ref "A-A") (pin "2") (pinfunction "S1_2") (pintype "passive"))
    )
    (net (code "78") (name "unconnected-(A-G-P1-Pad4)") (class "Default")
      (node (ref "A-G") (pin "4") (pinfunction "P1_4") (pintype "passive"))
    )
    (net (code "79") (name "unconnected-(A-G-S1-Pad2)") (class "Default")
      (node (ref "A-G") (pin "2") (pinfunction "S1_2") (pintype "passive"))
    )
    (net (code "80") (name "unconnected-(COM_1-P-Pad3)") (class "Default")
      (node (ref "COM_1") (pin "3") (pinfunction "P_3") (pintype "passive"))
    )
    (net (code "81") (name "unconnected-(COM_1-S1-Pad2)") (class "Default")
      (node (ref "COM_1") (pin "2") (pinfunction "S1_2") (pintype "passive"))
    )
    (net (code "82") (name "unconnected-(COM_2-P-Pad3)") (class "Default")
      (node (ref "COM_2") (pin "3") (pinfunction "P_3") (pintype "passive"))
    )
    (net (code "83") (name "unconnected-(COM_2-S1-Pad2)") (class "Default")
      (node (ref "COM_2") (pin "2") (pinfunction "S1_2") (pintype "passive"))
    )
    (net (code "84") (name "unconnected-(ENTER-P1-Pad4)") (class "Default")
      (node (ref "ENTER") (pin "4") (pinfunction "P1_4") (pintype "passive"))
    )
    (net (code "85") (name "unconnected-(ENTER-S1-Pad2)") (class "Default")
      (node (ref "ENTER") (pin "2") (pinfunction "S1_2") (pintype "passive"))
    )
    (net (code "86") (name "unconnected-(FLIR_DN-P1-Pad4)") (class "Default")
      (node (ref "FLIR_DN") (pin "4") (pinfunction "P1_4") (pintype "passive"))
    )
    (net (code "87") (name "unconnected-(FLIR_DN-S1-Pad2)") (class "Default")
      (node (ref "FLIR_DN") (pin "2") (pinfunction "S1_2") (pintype "passive"))
    )
    (net (code "88") (name "unconnected-(FLIR_UP-P1-Pad4)") (class "Default")
      (node (ref "FLIR_UP") (pin "4") (pinfunction "P1_4") (pintype "passive"))
    )
    (net (code "89") (name "unconnected-(FLIR_UP-S1-Pad2)") (class "Default")
      (node (ref "FLIR_UP") (pin "2") (pinfunction "S1_2") (pintype "passive"))
    )
    (net (code "90") (name "unconnected-(IC1-1_(ADA3)PA3-Pad1)") (class "Default")
      (node (ref "IC1") (pin "1") (pinfunction "1_(ADA3)PA3_1") (pintype "bidirectional"))
    )
    (net (code "91") (name "unconnected-(IC1-2_(ADA4)PA4-Pad2)") (class "Default")
      (node (ref "IC1") (pin "2") (pinfunction "2_(ADA4)PA4_2") (pintype "bidirectional"))
    )
    (net (code "92") (name "unconnected-(IC1-3_(ADA5)PA5-Pad3)") (class "Default")
      (node (ref "IC1") (pin "3") (pinfunction "3_(ADA5)PA5_3") (pintype "bidirectional"))
    )
    (net (code "93") (name "unconnected-(IC1-4_(ADA6)PA6-Pad4)") (class "Default")
      (node (ref "IC1") (pin "4") (pinfunction "4_(ADA6)PA6_4") (pintype "bidirectional"))
    )
    (net (code "94") (name "unconnected-(IC1-5_(ACAOUT{slash}ADA7)PA7-Pad5)") (class "Default")
      (node (ref "IC1") (pin "5") (pinfunction "5_(ACAOUT/ADA7)PA7_5") (pintype "bidirectional"))
    )
    (net (code "95") (name "unconnected-(IC1-6_(AREFB{slash}ADB0)PB0-Pad6)") (class "Default")
      (node (ref "IC1") (pin "6") (pinfunction "6_(AREFB/ADB0)PB0_6") (pintype "bidirectional"))
    )
    (net (code "96") (name "unconnected-(IC1-7_(ADB1)PB1-Pad7)") (class "Default")
      (node (ref "IC1") (pin "7") (pinfunction "7_(ADB1)PB1_7") (pintype "bidirectional"))
    )
    (net (code "97") (name "unconnected-(IC1-8_(DAC0{slash}ADB2)PB2-Pad8)") (class "Default")
      (node (ref "IC1") (pin "8") (pinfunction "8_(DAC0/ADB2)PB2_8") (pintype "bidirectional"))
    )
    (net (code "98") (name "unconnected-(IC1-9_(DAC1{slash}ADB3)PB3-Pad9)") (class "Default")
      (node (ref "IC1") (pin "9") (pinfunction "9_(DAC1/ADB3)PB3_9") (pintype "bidirectional"))
    )
    (net (code "99") (name "unconnected-(IC1-10_(TMS{slash}ADB4)PB4-Pad10)") (class "Default")
      (node (ref "IC1") (pin "10") (pinfunction "10_(TMS/ADB4)PB4_10") (pintype "bidirectional"))
    )
    (net (code "100") (name "unconnected-(IC1-11_(TDI{slash}ADB5)PB5-Pad11)") (class "Default")
      (node (ref "IC1") (pin "11") (pinfunction "11_(TDI/ADB5)PB5_11") (pintype "bidirectional"))
    )
    (net (code "101") (name "unconnected-(IC1-12_(TCK{slash}ADB6)PB6-Pad12)") (class "Default")
      (node (ref "IC1") (pin "12") (pinfunction "12_(TCK/ADB6)PB6_12") (pintype "bidirectional"))
    )
    (net (code "102") (name "unconnected-(IC1-13_(TDO{slash}ACBOUT{slash}ADB7)PB7-Pad13)") (class "Default")
      (node (ref "IC1") (pin "13") (pinfunction "13_(TDO/ACBOUT/ADB7)PB7_13") (pintype "bidirectional"))
    )
    (net (code "103") (name "unconnected-(IC1-60_GND-Pad60)") (class "Default")
      (node (ref "IC1") (pin "60") (pinfunction "60_GND_60") (pintype "bidirectional"))
    )
    (net (code "104") (name "unconnected-(IC1-61_AVCC-Pad61)") (class "Default")
      (node (ref "IC1") (pin "61") (pinfunction "61_AVCC_61") (pintype "bidirectional"))
    )
    (net (code "105") (name "unconnected-(IC1-62_(AREFA{slash}ADA0)PA0-Pad62)") (class "Default")
      (node (ref "IC1") (pin "62") (pinfunction "62_(AREFA/ADA0)PA0_62") (pintype "bidirectional"))
    )
    (net (code "106") (name "unconnected-(IC1-63_(ADA1)PA1-Pad63)") (class "Default")
      (node (ref "IC1") (pin "63") (pinfunction "63_(ADA1)PA1_63") (pintype "bidirectional"))
    )
    (net (code "107") (name "unconnected-(IC1-64_(ADA2)PA2-Pad64)") (class "Default")
      (node (ref "IC1") (pin "64") (pinfunction "64_(ADA2)PA2_64") (pintype "bidirectional"))
    )
    (net (code "108") (name "unconnected-(IFF-P-Pad3)") (class "Default")
      (node (ref "IFF") (pin "3") (pinfunction "P_3") (pintype "passive"))
    )
    (net (code "109") (name "unconnected-(IFF-S1-Pad2)") (class "Default")
      (node (ref "IFF") (pin "2") (pinfunction "S1_2") (pintype "passive"))
    )
    (net (code "110") (name "unconnected-(JP1-Pad3)") (class "Default")
      (node (ref "JP1") (pin "3") (pinfunction "3_3") (pintype "passive"))
    )
    (net (code "111") (name "unconnected-(JP1-Pad4)") (class "Default")
      (node (ref "JP1") (pin "4") (pinfunction "4_4") (pintype "passive"))
    )
    (net (code "112") (name "unconnected-(LIST-P-Pad3)") (class "Default")
      (node (ref "LIST") (pin "3") (pinfunction "P_3") (pintype "passive"))
    )
    (net (code "113") (name "unconnected-(LIST-S1-Pad2)") (class "Default")
      (node (ref "LIST") (pin "2") (pinfunction "S1_2") (pintype "passive"))
    )
    (net (code "114") (name "unconnected-(RCL-P1-Pad4)") (class "Default")
      (node (ref "RCL") (pin "4") (pinfunction "P1_4") (pintype "passive"))
    )
    (net (code "115") (name "unconnected-(RCL-S1-Pad2)") (class "Default")
      (node (ref "RCL") (pin "2") (pinfunction "S1_2") (pintype "passive"))
    )
    (net (code "116") (name "unconnected-(STP_DN-P-Pad3)") (class "Default")
      (node (ref "STP_DN") (pin "3") (pinfunction "P_3") (pintype "passive"))
    )
    (net (code "117") (name "unconnected-(STP_DN-S1-Pad2)") (class "Default")
      (node (ref "STP_DN") (pin "2") (pinfunction "S1_2") (pintype "passive"))
    )
    (net (code "118") (name "unconnected-(STP_UP-P-Pad3)") (class "Default")
      (node (ref "STP_UP") (pin "3") (pinfunction "P_3") (pintype "passive"))
    )
    (net (code "119") (name "unconnected-(STP_UP-S1-Pad2)") (class "Default")
      (node (ref "STP_UP") (pin "2") (pinfunction "S1_2") (pintype "passive"))
    )
    (net (code "120") (name "unconnected-(TM1-PadE)") (class "Default")
      (node (ref "TM1") (pin "E") (pinfunction "E_E") (pintype "passive"))
    )
    (net (code "121") (name "unconnected-(U$1-PadCENTER)") (class "Default")
      (node (ref "U$1") (pin "CENTER") (pinfunction "CENTER_CENTER") (pintype "passive"))
    )
    (net (code "122") (name "unconnected-(WX-P-Pad3)") (class "Default")
      (node (ref "WX") (pin "3") (pinfunction "P_3") (pintype "passive"))
    )
    (net (code "123") (name "unconnected-(WX-S1-Pad2)") (class "Default")
      (node (ref "WX") (pin "2") (pinfunction "S1_2") (pintype "passive"))
    )
  )
)
